# LED-bas.net
KiCad netlist of a schematic drawn in EAGLE
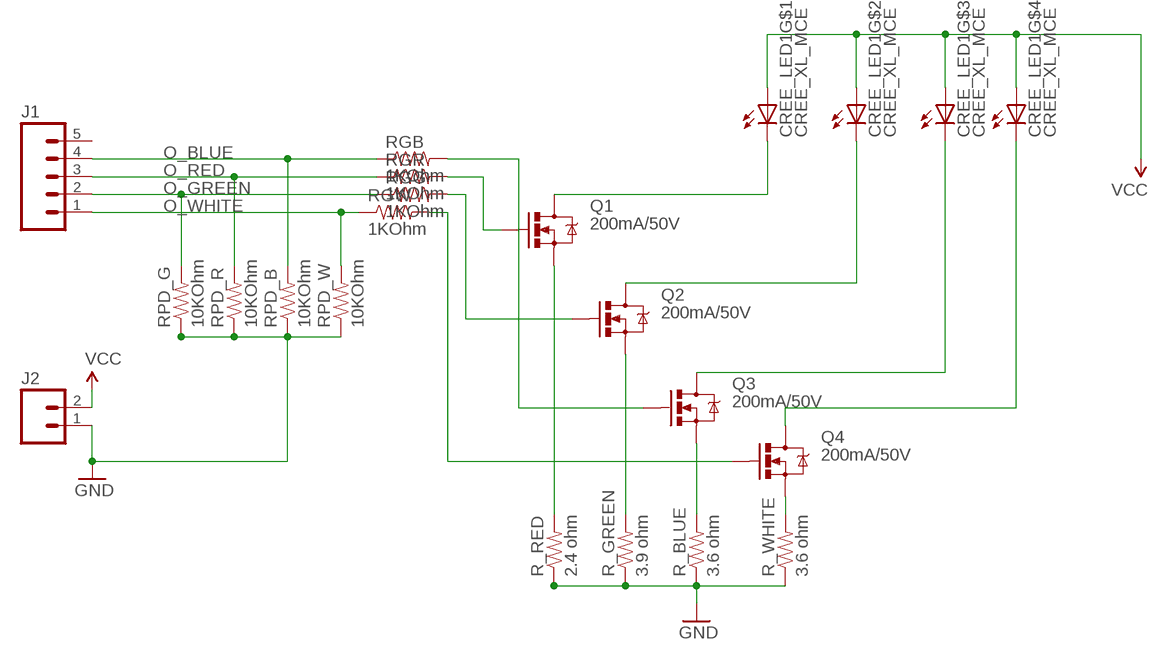
[diagram p0: schematic, sheet 1]

(export (version "E")
  (design (tool "Eeschema 10.0.6"))
  (components
    (comp (ref "CREE_LED1")
      (value "CREE_XL_MCE")
      (footprint "eagle-import:CREE_XL_MCE")
      (libsource (lib "eagle-import") (part "CREE_XL_MCE"))
    )
    (comp (ref "J1")
      (value "M05NO_SILK")
      (footprint "eagle-import:1X05_NO_SILK")
      (libsource (lib "eagle-import") (part "M05NO_SILK"))
    )
    (comp (ref "J2")
      (value "M021X02_NO_SILK")
      (footprint "eagle-import:1X02_NO_SILK")
      (libsource (lib "eagle-import") (part "M021X02_NO_SILK"))
    )
    (comp (ref "Q1")
      (value "200mA/50V")
      (footprint "eagle-import:SOT23-3")
      (libsource (lib "eagle-import") (part "MOSFET-NCHANNELBSS138"))
    )
    (comp (ref "Q2")
      (value "200mA/50V")
      (footprint "eagle-import:SOT23-3")
      (libsource (lib "eagle-import") (part "MOSFET-NCHANNELBSS138"))
    )
    (comp (ref "Q3")
      (value "200mA/50V")
      (footprint "eagle-import:SOT23-3")
      (libsource (lib "eagle-import") (part "MOSFET-NCHANNELBSS138"))
    )
    (comp (ref "Q4")
      (value "200mA/50V")
      (footprint "eagle-import:SOT23-3")
      (libsource (lib "eagle-import") (part "MOSFET-NCHANNELBSS138"))
    )
    (comp (ref "RGB")
      (value "1KOhm")
      (footprint "eagle-import:0805")
      (libsource (lib "eagle-import") (part "RESISTOR0805-RES"))
    )
    (comp (ref "RGG")
      (value "1KOhm")
      (footprint "eagle-import:0805")
      (libsource (lib "eagle-import") (part "RESISTOR0805-RES"))
    )
    (comp (ref "RGR")
      (value "1KOhm")
      (footprint "eagle-import:0805")
      (libsource (lib "eagle-import") (part "RESISTOR0805-RES"))
    )
    (comp (ref "RGW")
      (value "1KOhm")
      (footprint "eagle-import:0805")
      (libsource (lib "eagle-import") (part "RESISTOR0805-RES"))
    )
    (comp (ref "RPD_B")
      (value "10KOhm")
      (footprint "eagle-import:0805")
      (libsource (lib "eagle-import") (part "RESISTOR0805-RES"))
    )
    (comp (ref "RPD_G")
      (value "10KOhm")
      (footprint "eagle-import:0805")
      (libsource (lib "eagle-import") (part "RESISTOR0805-RES"))
    )
    (comp (ref "RPD_R")
      (value "10KOhm")
      (footprint "eagle-import:0805")
      (libsource (lib "eagle-import") (part "RESISTOR0805-RES"))
    )
    (comp (ref "RPD_W")
      (value "10KOhm")
      (footprint "eagle-import:0805")
      (libsource (lib "eagle-import") (part "RESISTOR0805-RES"))
    )
    (comp (ref "R_BLUE")
      (value "3.6 ohm")
      (footprint "eagle-import:0805")
      (libsource (lib "eagle-import") (part "RESISTOR0805-RES"))
    )
    (comp (ref "R_GREEN")
      (value "3.9 ohm")
      (footprint "eagle-import:0805")
      (libsource (lib "eagle-import") (part "RESISTOR0805-RES"))
    )
    (comp (ref "R_RED")
      (value "2.4 ohm")
      (footprint "eagle-import:0805")
      (libsource (lib "eagle-import") (part "RESISTOR0805-RES"))
    )
    (comp (ref "R_WHITE")
      (value "3.6 ohm")
      (footprint "eagle-import:0805")
      (libsource (lib "eagle-import") (part "RESISTOR0805-RES"))
    )
  )
  (nets
    (net (code "1") (name "/O_BLUE") (class "Default")
      (node (ref "J1") (pin "4") (pinfunction "4_4") (pintype "passive"))
      (node (ref "RGB") (pin "1") (pinfunction "1_1") (pintype "passive"))
      (node (ref "RPD_B") (pin "2") (pinfunction "2_2") (pintype "passive"))
    )
    (net (code "2") (name "/O_GREEN") (class "Default")
      (node (ref "J1") (pin "2") (pinfunction "2_2") (pintype "passive"))
      (node (ref "RGG") (pin "1") (pinfunction "1_1") (pintype "passive"))
      (node (ref "RPD_G") (pin "2") (pinfunction "2_2") (pintype "passive"))
    )
    (net (code "3") (name "/O_RED") (class "Default")
      (node (ref "J1") (pin "3") (pinfunction "3_3") (pintype "passive"))
      (node (ref "RGR") (pin "1") (pinfunction "1_1") (pintype "passive"))
      (node (ref "RPD_R") (pin "2") (pinfunction "2_2") (pintype "passive"))
    )
    (net (code "4") (name "/O_WHITE") (class "Default")
      (node (ref "J1") (pin "1") (pinfunction "1_1") (pintype "passive"))
      (node (ref "RGW") (pin "1") (pinfunction "1_1") (pintype "passive"))
      (node (ref "RPD_W") (pin "2") (pinfunction "2_2") (pintype "passive"))
    )
    (net (code "5") (name "GND") (class "Default")
      (node (ref "J2") (pin "1") (pinfunction "1_1") (pintype "passive"))
      (node (ref "RPD_B") (pin "1") (pinfunction "1_1") (pintype "passive"))
      (node (ref "RPD_G") (pin "1") (pinfunction "1_1") (pintype "passive"))
      (node (ref "RPD_R") (pin "1") (pinfunction "1_1") (pintype "passive"))
      (node (ref "RPD_W") (pin "1") (pinfunction "1_1") (pintype "passive"))
      (node (ref "R_BLUE") (pin "1") (pinfunction "1_1") (pintype "passive"))
      (node (ref "R_GREEN") (pin "1") (pinfunction "1_1") (pintype "passive"))
      (node (ref "R_RED") (pin "1") (pinfunction "1_1") (pintype "passive"))
      (node (ref "R_WHITE") (pin "1") (pinfunction "1_1") (pintype "passive"))
    )
    (net (code "6") (name "Net-(CREE_LED1A-C)") (class "Default")
      (node (ref "CREE_LED1") (pin "8") (pinfunction "C_8") (pintype "passive"))
      (node (ref "Q1") (pin "3") (pinfunction "D_3") (pintype "passive"))
    )
    (net (code "7") (name "Net-(CREE_LED1B-C)") (class "Default")
      (node (ref "CREE_LED1") (pin "7") (pinfunction "C_7") (pintype "passive"))
      (node (ref "Q2") (pin "3") (pinfunction "D_3") (pintype "passive"))
    )
    (net (code "8") (name "Net-(CREE_LED1C-C)") (class "Default")
      (node (ref "CREE_LED1") (pin "6") (pinfunction "C_6") (pintype "passive"))
      (node (ref "Q3") (pin "3") (pinfunction "D_3") (pintype "passive"))
    )
    (net (code "9") (name "Net-(CREE_LED1D-C)") (class "Default")
      (node (ref "CREE_LED1") (pin "5") (pinfunction "C_5") (pintype "passive"))
      (node (ref "Q4") (pin "3") (pinfunction "D_3") (pintype "passive"))
    )
    (net (code "10") (name "Net-(Q1-G)") (class "Default")
      (node (ref "Q1") (pin "1") (pinfunction "G_1") (pintype "passive"))
      (node (ref "RGR") (pin "2") (pinfunction "2_2") (pintype "passive"))
    )
    (net (code "11") (name "Net-(Q1-S)") (class "Default")
      (node (ref "Q1") (pin "2") (pinfunction "S_2") (pintype "passive"))
      (node (ref "R_RED") (pin "2") (pinfunction "2_2") (pintype "passive"))
    )
    (net (code "12") (name "Net-(Q2-G)") (class "Default")
      (node (ref "Q2") (pin "1") (pinfunction "G_1") (pintype "passive"))
      (node (ref "RGG") (pin "2") (pinfunction "2_2") (pintype "passive"))
    )
    (net (code "13") (name "Net-(Q2-S)") (class "Default")
      (node (ref "Q2") (pin "2") (pinfunction "S_2") (pintype "passive"))
      (node (ref "R_GREEN") (pin "2") (pinfunction "2_2") (pintype "passive"))
    )
    (net (code "14") (name "Net-(Q3-G)") (class "Default")
      (node (ref "Q3") (pin "1") (pinfunction "G_1") (pintype "passive"))
      (node (ref "RGB") (pin "2") (pinfunction "2_2") (pintype "passive"))
    )
    (net (code "15") (name "Net-(Q3-S)") (class "Default")
      (node (ref "Q3") (pin "2") (pinfunction "S_2") (pintype "passive"))
      (node (ref "R_BLUE") (pin "2") (pinfunction "2_2") (pintype "passive"))
    )
    (net (code "16") (name "Net-(Q4-G)") (class "Default")
      (node (ref "Q4") (pin "1") (pinfunction "G_1") (pintype "passive"))
      (node (ref "RGW") (pin "2") (pinfunction "2_2") (pintype "passive"))
    )
    (net (code "17") (name "Net-(Q4-S)") (class "Default")
      (node (ref "Q4") (pin "2") (pinfunction "S_2") (pintype "passive"))
      (node (ref "R_WHITE") (pin "2") (pinfunction "2_2") (pintype "passive"))
    )
    (net (code "18") (name "VCC") (class "Default")
      (node (ref "CREE_LED1") (pin "1") (pinfunction "A_1") (pintype "passive"))
      (node (ref "CREE_LED1") (pin "2") (pinfunction "A_2") (pintype "passive"))
      (node (ref "CREE_LED1") (pin "3") (pinfunction "A_3") (pintype "passive"))
      (node (ref "CREE_LED1") (pin "4") (pinfunction "A_4") (pintype "passive"))
      (node (ref "J2") (pin "2") (pinfunction "2_2") (pintype "passive"))
    )
    (net (code "19") (name "unconnected-(J1-Pad5)") (class "Default")
      (node (ref "J1") (pin "5") (pinfunction "5_5") (pintype "passive"))
    )
  )
)
